# BatteryMonitor.net
KiCad netlist of a schematic drawn in Altium Designer
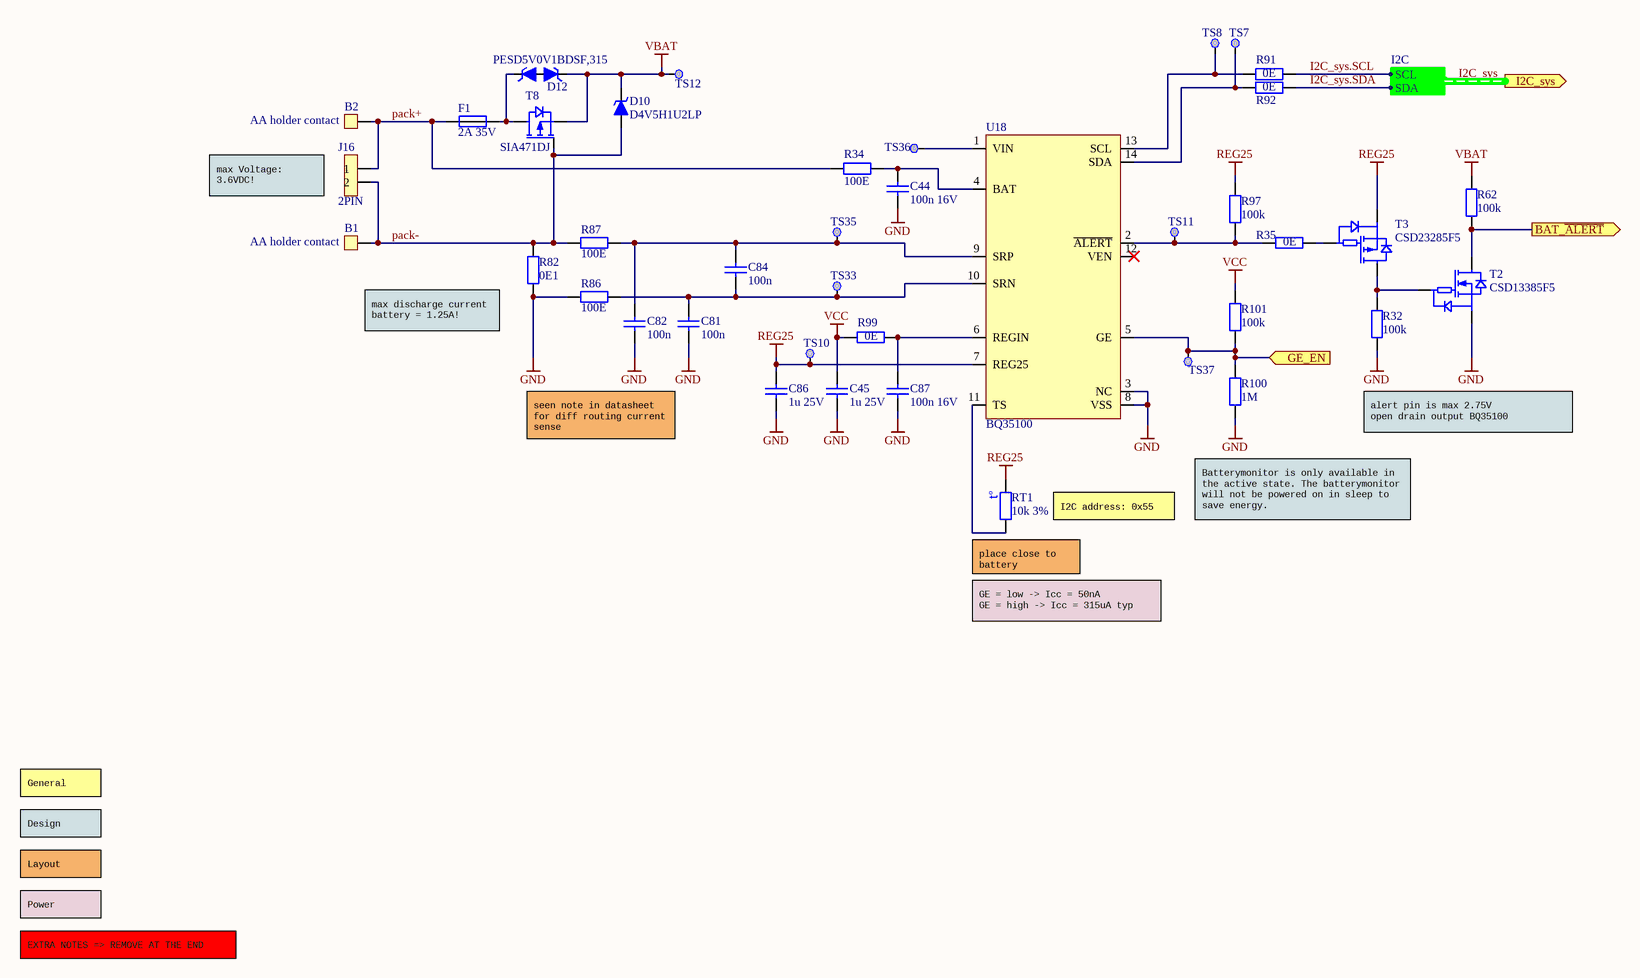
[diagram p0: BatteryMonitor.SchDoc]

(export (version "E")
  (design (tool "Eeschema 10.0.6"))
  (components
    (comp (ref "B1")
      (value "AA holder contact")
      (footprint "ADD-900G002-000")
      (description "Battery holder for AA cell")
      (libsource (lib "DCI") (part "Battery_contact"))
    )
    (comp (ref "B2")
      (value "AA holder contact")
      (footprint "ADD-900G002-000")
      (description "Battery holder for AA cell")
      (libsource (lib "DCI") (part "Battery_contact"))
    )
    (comp (ref "C44")
      (value "100n 16V")
      (footprint "CAPC1005X05N")
      (description "100nF, 16V, 10%, X7R")
      (libsource (lib "DCI") (part "Capacitor_NP"))
    )
    (comp (ref "C45")
      (value "1u 25V")
      (footprint "CAPC1608X09N")
      (description "1UF, 25V, 10%, 0603, X7R")
      (libsource (lib "DCI") (part "Capacitor_NP"))
    )
    (comp (ref "C81")
      (value "100n")
      (footprint "CAPC1608X09N")
      (description "100nF 50V 10% X7R")
      (libsource (lib "DCI") (part "Capacitor_NP"))
    )
    (comp (ref "C82")
      (value "100n")
      (footprint "CAPC1608X09N")
      (description "100nF 50V 10% X7R")
      (libsource (lib "DCI") (part "Capacitor_NP"))
    )
    (comp (ref "C84")
      (value "100n")
      (footprint "CAPC1608X09N")
      (description "100nF 50V 10% X7R")
      (libsource (lib "DCI") (part "Capacitor_NP"))
    )
    (comp (ref "C86")
      (value "1u 25V")
      (footprint "CAPC1608X09N")
      (description "1UF, 25V, 10%, 0603, X7R")
      (libsource (lib "DCI") (part "Capacitor_NP"))
    )
    (comp (ref "C87")
      (value "100n 16V")
      (footprint "CAPC1005X05N")
      (description "100nF, 16V, 10%, X7R")
      (libsource (lib "DCI") (part "Capacitor_NP"))
    )
    (comp (ref "D10")
      (value "D4V5H1U2LP")
      (footprint "DFN110P160X55-2N")
      (description "TVS diode 4,5V unidirec")
      (libsource (lib "DCI") (part "D_TVS"))
    )
    (comp (ref "D12")
      (value "PESD5V0V1BDSF,315")
      (footprint "DIO-000G003-002")
      (description "TVS diode 5V bidirec")
      (libsource (lib "DCI") (part "D_TVS_BI_1"))
    )
    (comp (ref "F1")
      (value "2A 35V")
      (footprint "Fuse1608X05N")
      (description "2A High inrush SMD")
      (libsource (lib "DCI") (part "FUSE"))
    )
    (comp (ref "J16")
      (value "2PIN")
      (footprint "JST-B2B-PH-SM4-TB")
      (description "JST PH 2p top entry 2A SMD")
      (libsource (lib "DCI") (part "2PIN"))
    )
    (comp (ref "R32")
      (value "100k")
      (footprint "RESC1005X04N")
      (description "100K, 62.5mW, 1%")
      (libsource (lib "DCI") (part "Resistor"))
    )
    (comp (ref "R34")
      (value "100E")
      (footprint "RESC1005X04N")
      (description "100E, 62.5mW, 1%")
      (libsource (lib "") (part "Resistor_2"))
    )
    (comp (ref "R35")
      (value "0E")
      (footprint "RESC1005X04N")
      (description "0E, 62.5mW, 1%")
      (libsource (lib "") (part "Resistor_1"))
    )
    (comp (ref "R62")
      (value "100k")
      (footprint "RESC1005X04N")
      (description "100K, 62.5mW, 1%")
      (libsource (lib "DCI") (part "Resistor"))
    )
    (comp (ref "R82")
      (value "0E1")
      (footprint "RESC3116X13L")
      (description "0E1 1% 0,5W 50ppm")
      (libsource (lib "DCI") (part "Resistor"))
    )
    (comp (ref "R86")
      (value "100E")
      (footprint "RESC1608X13N")
      (description "100E 100mW, 1%")
      (libsource (lib "") (part "Resistor_1"))
    )
    (comp (ref "R87")
      (value "100E")
      (footprint "RESC1608X13N")
      (description "100E 100mW, 1%")
      (libsource (lib "") (part "Resistor_1"))
    )
    (comp (ref "R91")
      (value "0E")
      (footprint "RESC1005X04N")
      (description "0E, 62.5mW, 1%")
      (libsource (lib "") (part "Resistor_1"))
    )
    (comp (ref "R92")
      (value "0E")
      (footprint "RESC1005X04N")
      (description "0E, 62.5mW, 1%")
      (libsource (lib "") (part "Resistor_1"))
    )
    (comp (ref "R97")
      (value "100k")
      (footprint "RESC1005X04N")
      (description "100K, 62.5mW, 1%")
      (libsource (lib "DCI") (part "Resistor"))
    )
    (comp (ref "R99")
      (value "0E")
      (footprint "RESC1005X04N")
      (description "0E, 62.5mW, 1%")
      (libsource (lib "") (part "Resistor_1"))
    )
    (comp (ref "R100")
      (value "1M")
      (footprint "RESC1005x04N")
      (description "1M, 62.5mW, 1%")
      (libsource (lib "DCI") (part "Resistor"))
    )
    (comp (ref "R101")
      (value "100k")
      (footprint "RESC1005X04N")
      (description "100K, 62.5mW, 1%")
      (libsource (lib "DCI") (part "Resistor"))
    )
    (comp (ref "RT1")
      (value "10k 3%")
      (footprint "RESC2013X14M")
      (description "NTC 10K 3% SMD 0805")
      (libsource (lib "DCI") (part "R_Thermal"))
    )
    (comp (ref "T2")
      (value "CSD13385F5")
      (footprint "DFN-500G000-003")
      (description "7.1A, 12V, N-channel FemtoFet")
      (libsource (lib "DCI") (part "MOSFET_CSD13385F5"))
    )
    (comp (ref "T3")
      (value "CSD23285F5")
      (footprint "DFN-500G000-003")
      (description "3.3A, 12V, P-channel FemtoFet")
      (libsource (lib "DCI") (part "MOSFET_CSD23285F5"))
    )
    (comp (ref "T8")
      (value "SIA471DJ")
      (footprint "PAK-SC70-6")
      (description "30V 12.9A 0.014E logic level")
      (libsource (lib "DCI") (part "P_Mosfet"))
    )
    (comp (ref "TS7")
      (value "TESTPAD")
      (footprint "TESTPAD 2MM")
      (description "0.5mm Testpad SMD")
      (libsource (lib "PCBComponenten") (part "TESTPAD"))
    )
    (comp (ref "TS8")
      (value "TESTPAD")
      (footprint "TESTPAD 2MM")
      (description "0.5mm Testpad SMD")
      (libsource (lib "PCBComponenten") (part "TESTPAD"))
    )
    (comp (ref "TS10")
      (value "TESTPAD")
      (footprint "TESTPAD 2MM")
      (description "0.5mm Testpad SMD")
      (libsource (lib "PCBComponenten") (part "TESTPAD"))
    )
    (comp (ref "TS11")
      (value "TESTPAD")
      (footprint "TESTPAD 2MM")
      (description "0.5mm Testpad SMD")
      (libsource (lib "PCBComponenten") (part "TESTPAD"))
    )
    (comp (ref "TS12")
      (value "TESTPAD")
      (footprint "TESTPAD 2MM")
      (description "0.5mm Testpad SMD")
      (libsource (lib "PCBComponenten") (part "TESTPAD"))
    )
    (comp (ref "TS33")
      (value "TESTPOINT")
      (footprint "testpad 1.5 mm")
      (libsource (lib "PCBComponenten") (part "TESTPOINT"))
    )
    (comp (ref "TS35")
      (value "TESTPOINT")
      (footprint "testpad 1.5 mm")
      (libsource (lib "PCBComponenten") (part "TESTPOINT"))
    )
    (comp (ref "TS36")
      (value "TESTPAD")
      (footprint "TESTPAD 2MM")
      (description "0.5mm Testpad SMD")
      (libsource (lib "PCBComponenten") (part "TESTPAD"))
    )
    (comp (ref "TS37")
      (value "TESTPAD")
      (footprint "TESTPAD 2MM")
      (description "0.5mm Testpad SMD")
      (libsource (lib "PCBComponenten") (part "TESTPAD"))
    )
    (comp (ref "U18")
      (value "BQ35100")
      (footprint "SOP-650G001-014")
      (description "Lithium Fuel Gauge")
      (libsource (lib "DCI") (part "sens_bat_fg_BQ35100PW"))
    )
  )
  (nets
    (net (code "2") (name "/BAT_~{ALERT}") (class "Default")
      (node (ref "R62") (pin "1") (pinfunction "1_1") (pintype "passive"))
      (node (ref "T2") (pin "D") (pinfunction "D_D") (pintype "passive"))
    )
    (net (code "3") (name "/GE_EN") (class "Default")
      (node (ref "R100") (pin "2") (pinfunction "2_2") (pintype "passive"))
      (node (ref "R101") (pin "1") (pinfunction "1_1") (pintype "passive"))
      (node (ref "TS37") (pin "1") (pinfunction "TP_1") (pintype "passive"))
      (node (ref "U18") (pin "5") (pinfunction "GE_5") (pintype "passive"))
    )
    (net (code "4") (name "/I2C_sys.SCL") (class "Default")
      (node (ref "R91") (pin "2") (pinfunction "2_2") (pintype "passive"))
    )
    (net (code "5") (name "/I2C_sys.SDA") (class "Default")
      (node (ref "R92") (pin "2") (pinfunction "2_2") (pintype "passive"))
    )
    (net (code "7") (name "/pack+") (class "Default")
      (node (ref "B2") (pin "1") (pinfunction "1_1") (pintype "power_in"))
      (node (ref "F1") (pin "2") (pinfunction "2_2") (pintype "passive"))
      (node (ref "J16") (pin "1") (pinfunction "1_1") (pintype "passive"))
      (node (ref "R34") (pin "1") (pinfunction "1_1") (pintype "passive"))
    )
    (net (code "8") (name "/pack-") (class "Default")
      (node (ref "B1") (pin "1") (pinfunction "1_1") (pintype "power_in"))
      (node (ref "D10") (pin "A") (pinfunction "A_A") (pintype "passive"))
      (node (ref "J16") (pin "2") (pinfunction "2_2") (pintype "passive"))
      (node (ref "R82") (pin "2") (pinfunction "2_2") (pintype "passive"))
      (node (ref "R87") (pin "1") (pinfunction "1_1") (pintype "passive"))
      (node (ref "T8") (pin "G") (pinfunction "G_G") (pintype "passive"))
    )
    (net (code "9") (name "GND") (class "Default")
      (node (ref "C44") (pin "1") (pinfunction "1_1") (pintype "passive"))
      (node (ref "C45") (pin "1") (pinfunction "1_1") (pintype "passive"))
      (node (ref "C81") (pin "1") (pinfunction "1_1") (pintype "passive"))
      (node (ref "C82") (pin "1") (pinfunction "1_1") (pintype "passive"))
      (node (ref "C86") (pin "1") (pinfunction "1_1") (pintype "passive"))
      (node (ref "C87") (pin "1") (pinfunction "1_1") (pintype "passive"))
      (node (ref "R100") (pin "1") (pinfunction "1_1") (pintype "passive"))
      (node (ref "R32") (pin "1") (pinfunction "1_1") (pintype "passive"))
      (node (ref "R82") (pin "1") (pinfunction "1_1") (pintype "passive"))
      (node (ref "R86") (pin "1") (pinfunction "1_1") (pintype "passive"))
      (node (ref "T2") (pin "S") (pinfunction "S_S") (pintype "passive"))
      (node (ref "U18") (pin "3") (pinfunction "NC_3") (pintype "passive"))
      (node (ref "U18") (pin "8") (pinfunction "VSS_8") (pintype "passive"))
    )
    (net (code "10") (name "Net-(D12-PadC2)") (class "Default")
      (node (ref "D12") (pin "C2") (pinfunction "C2_C2") (pintype "passive"))
      (node (ref "F1") (pin "1") (pinfunction "1_1") (pintype "passive"))
      (node (ref "T8") (pin "D") (pinfunction "D_D") (pintype "passive"))
    )
    (net (code "11") (name "Net-(R32-Pad2)") (class "Default")
      (node (ref "R32") (pin "2") (pinfunction "2_2") (pintype "passive"))
      (node (ref "T2") (pin "G") (pinfunction "G_G") (pintype "passive"))
      (node (ref "T3") (pin "D") (pinfunction "D_D") (pintype "passive"))
    )
    (net (code "12") (name "Net-(R35-Pad2)") (class "Default")
      (node (ref "R35") (pin "2") (pinfunction "2_2") (pintype "passive"))
      (node (ref "T3") (pin "G") (pinfunction "G_G") (pintype "passive"))
    )
    (net (code "13") (name "Net-(TS7-TP)") (class "Default")
      (node (ref "R92") (pin "1") (pinfunction "1_1") (pintype "passive"))
      (node (ref "TS7") (pin "1") (pinfunction "TP_1") (pintype "passive"))
      (node (ref "U18") (pin "14") (pinfunction "SDA_14") (pintype "passive"))
    )
    (net (code "14") (name "Net-(TS8-TP)") (class "Default")
      (node (ref "R91") (pin "1") (pinfunction "1_1") (pintype "passive"))
      (node (ref "TS8") (pin "1") (pinfunction "TP_1") (pintype "passive"))
      (node (ref "U18") (pin "13") (pinfunction "SCL_13") (pintype "passive"))
    )
    (net (code "15") (name "Net-(TS11-TP)") (class "Default")
      (node (ref "R35") (pin "1") (pinfunction "1_1") (pintype "passive"))
      (node (ref "R97") (pin "1") (pinfunction "1_1") (pintype "passive"))
      (node (ref "TS11") (pin "1") (pinfunction "TP_1") (pintype "passive"))
      (node (ref "U18") (pin "2") (pinfunction "~{ALERT}_2") (pintype "passive"))
    )
    (net (code "16") (name "Net-(TS33-TP)") (class "Default")
      (node (ref "C81") (pin "2") (pinfunction "2_2") (pintype "passive"))
      (node (ref "C84") (pin "1") (pinfunction "1_1") (pintype "passive"))
      (node (ref "R86") (pin "2") (pinfunction "2_2") (pintype "passive"))
      (node (ref "TS33") (pin "1") (pinfunction "TP_1") (pintype "passive"))
      (node (ref "U18") (pin "10") (pinfunction "SRN_10") (pintype "passive"))
    )
    (net (code "17") (name "Net-(TS35-TP)") (class "Default")
      (node (ref "C82") (pin "2") (pinfunction "2_2") (pintype "passive"))
      (node (ref "C84") (pin "2") (pinfunction "2_2") (pintype "passive"))
      (node (ref "R87") (pin "2") (pinfunction "2_2") (pintype "passive"))
      (node (ref "TS35") (pin "1") (pinfunction "TP_1") (pintype "passive"))
      (node (ref "U18") (pin "9") (pinfunction "SRP_9") (pintype "passive"))
    )
    (net (code "18") (name "Net-(TS36-TP)") (class "Default")
      (node (ref "TS36") (pin "1") (pinfunction "TP_1") (pintype "passive"))
      (node (ref "U18") (pin "1") (pinfunction "VIN_1") (pintype "passive"))
    )
    (net (code "19") (name "Net-(U18-BAT)") (class "Default")
      (node (ref "C44") (pin "2") (pinfunction "2_2") (pintype "passive"))
      (node (ref "R34") (pin "2") (pinfunction "2_2") (pintype "passive"))
      (node (ref "U18") (pin "4") (pinfunction "BAT_4") (pintype "passive"))
    )
    (net (code "20") (name "Net-(U18-REGIN)") (class "Default")
      (node (ref "C87") (pin "2") (pinfunction "2_2") (pintype "passive"))
      (node (ref "R99") (pin "2") (pinfunction "2_2") (pintype "passive"))
      (node (ref "U18") (pin "6") (pinfunction "REGIN_6") (pintype "passive"))
    )
    (net (code "21") (name "Net-(U18-TS)") (class "Default")
      (node (ref "RT1") (pin "2") (pinfunction "2_2") (pintype "passive"))
      (node (ref "U18") (pin "11") (pinfunction "TS_11") (pintype "passive"))
    )
    (net (code "22") (name "REG25") (class "Default")
      (node (ref "C86") (pin "2") (pinfunction "2_2") (pintype "passive"))
      (node (ref "R97") (pin "2") (pinfunction "2_2") (pintype "passive"))
      (node (ref "RT1") (pin "1") (pinfunction "1_1") (pintype "passive"))
      (node (ref "T3") (pin "S") (pinfunction "S_S") (pintype "passive"))
      (node (ref "TS10") (pin "1") (pinfunction "TP_1") (pintype "passive"))
      (node (ref "U18") (pin "7") (pinfunction "REG25_7") (pintype "passive"))
    )
    (net (code "23") (name "VBAT") (class "Default")
      (node (ref "D10") (pin "C") (pinfunction "C_C") (pintype "passive"))
      (node (ref "D12") (pin "C1") (pinfunction "C1_C1") (pintype "passive"))
      (node (ref "R62") (pin "2") (pinfunction "2_2") (pintype "passive"))
      (node (ref "T8") (pin "S") (pinfunction "S_S") (pintype "passive"))
      (node (ref "TS12") (pin "1") (pinfunction "TP_1") (pintype "passive"))
    )
    (net (code "24") (name "VCC") (class "Default")
      (node (ref "C45") (pin "2") (pinfunction "2_2") (pintype "passive"))
      (node (ref "R101") (pin "2") (pinfunction "2_2") (pintype "passive"))
      (node (ref "R99") (pin "1") (pinfunction "1_1") (pintype "passive"))
    )
    (net (code "25") (name "unconnected-(U18-VEN-Pad12)") (class "Default")
      (node (ref "U18") (pin "12") (pinfunction "VEN_12") (pintype "passive+no_connect"))
    )
  )
)
